# tuggerTrackerV1.net
KiCad netlist of a schematic drawn in EAGLE
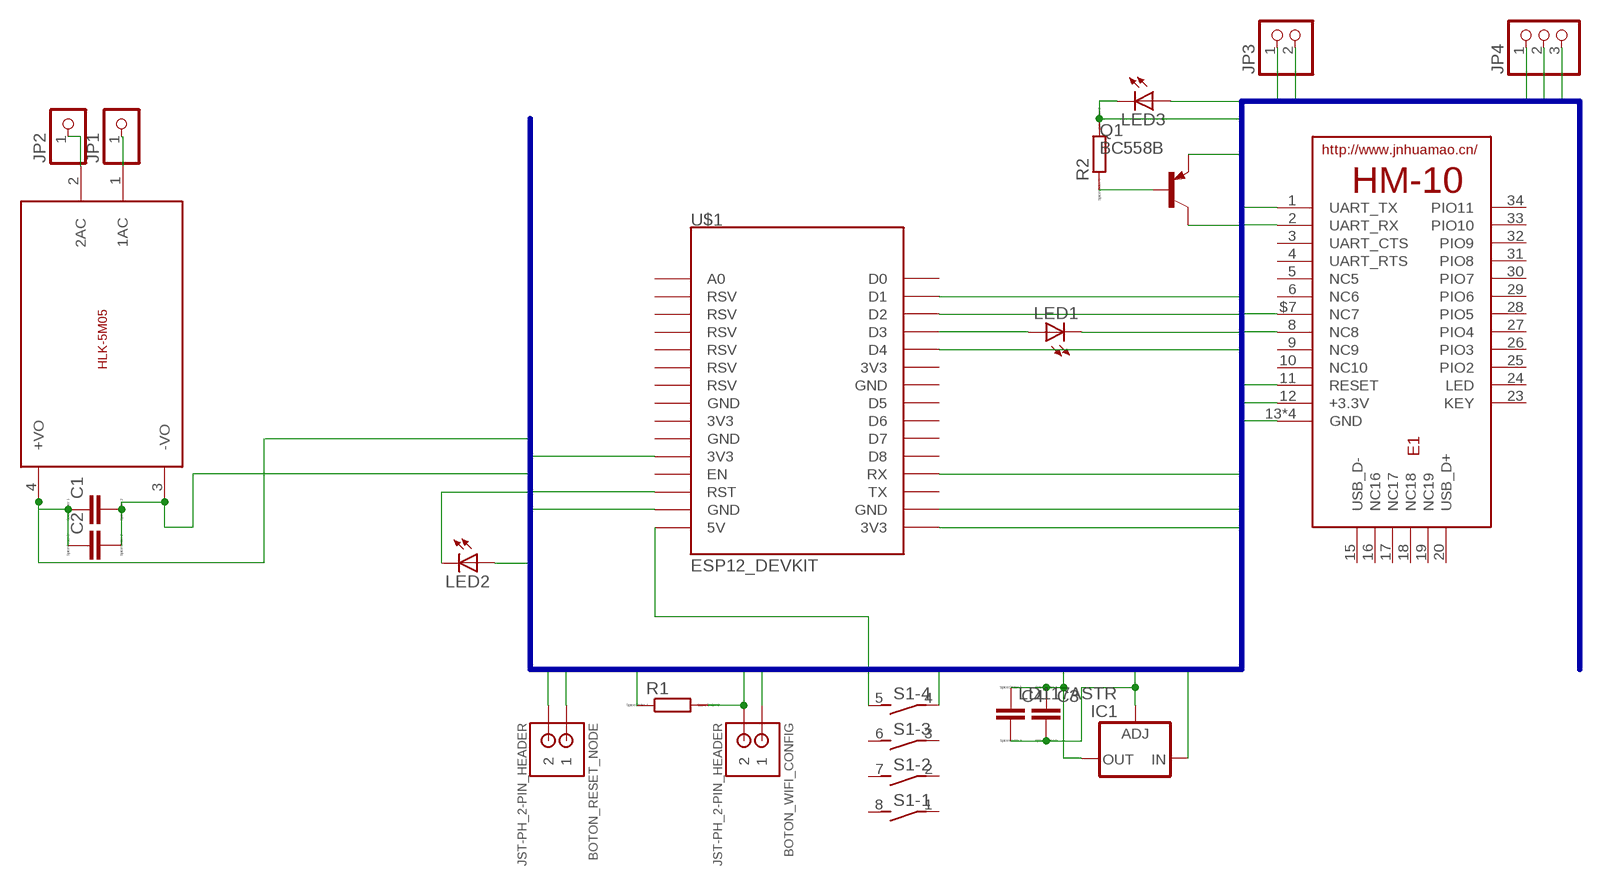
[diagram p0: schematic, sheet 1]

(export (version "E")
  (design (tool "Eeschema 10.0.6"))
  (components
    (comp (ref "BOTON_RESET_NODE")
      (value "JST-PH_2-PIN_HEADER")
      (footprint "eagle-import:JST_B2B-PH_HEADER")
      (libsource (lib "eagle-import") (part "JST-PH_2-PIN_HEADER"))
    )
    (comp (ref "BOTON_WIFI_CONFIG")
      (value "JST-PH_2-PIN_HEADER")
      (footprint "eagle-import:JST_B2B-PH_HEADER")
      (libsource (lib "eagle-import") (part "JST-PH_2-PIN_HEADER"))
    )
    (comp (ref "C1")
      (value "CC0603")
      (footprint "eagle-import:C0603")
      (libsource (lib "eagle-import") (part "CC0603"))
    )
    (comp (ref "C2")
      (value "CC0603")
      (footprint "eagle-import:C0603")
      (libsource (lib "eagle-import") (part "CC0603"))
    )
    (comp (ref "C3")
      (value "CC0603")
      (footprint "eagle-import:C0603")
      (libsource (lib "eagle-import") (part "CC0603"))
    )
    (comp (ref "C4")
      (value "CC0603")
      (footprint "eagle-import:C0603")
      (libsource (lib "eagle-import") (part "CC0603"))
    )
    (comp (ref "E1")
      (value "HM-10-BOARD")
      (footprint "eagle-import:26.9X13X2.2_BOARD")
      (libsource (lib "eagle-import") (part "HM-10-BOARD"))
    )
    (comp (ref "IC1")
      (value "LD117ASTR")
      (footprint "eagle-import:SOT223")
      (libsource (lib "eagle-import") (part "LD117A?STR"))
    )
    (comp (ref "JP1")
      (value "PINHD-1X1")
      (footprint "eagle-import:1X01")
      (libsource (lib "eagle-import") (part "PINHD-1X1"))
    )
    (comp (ref "JP2")
      (value "PINHD-1X1")
      (footprint "eagle-import:1X01")
      (libsource (lib "eagle-import") (part "PINHD-1X1"))
    )
    (comp (ref "JP3")
      (value "PINHD-1X2")
      (footprint "eagle-import:1X02")
      (libsource (lib "eagle-import") (part "PINHD-1X2"))
    )
    (comp (ref "JP4")
      (value "PINHD-1X3")
      (footprint "eagle-import:1X03")
      (libsource (lib "eagle-import") (part "PINHD-1X3"))
    )
    (comp (ref "LED1")
      (value "LEDCHIPLED_1206")
      (footprint "eagle-import:CHIPLED_1206")
      (libsource (lib "eagle-import") (part "LEDCHIPLED_1206"))
    )
    (comp (ref "LED2")
      (value "LEDCHIPLED_1206")
      (footprint "eagle-import:CHIPLED_1206")
      (libsource (lib "eagle-import") (part "LEDCHIPLED_1206"))
    )
    (comp (ref "LED3")
      (value "LEDCHIPLED_1206")
      (footprint "eagle-import:CHIPLED_1206")
      (libsource (lib "eagle-import") (part "LEDCHIPLED_1206"))
    )
    (comp (ref "Q1")
      (value "BC558B")
      (footprint "eagle-import:TO92-EBC")
      (libsource (lib "eagle-import") (part "BC558B"))
    )
    (comp (ref "R1")
      (value "R0207/10")
      (footprint "eagle-import:0207_10")
      (libsource (lib "eagle-import") (part "R0207/10"))
    )
    (comp (ref "R2")
      (value "R0207/10")
      (footprint "eagle-import:0207_10")
      (libsource (lib "eagle-import") (part "R0207/10"))
    )
    (comp (ref "S1")
      (value "DIP04S")
      (footprint "eagle-import:DIP04S")
      (libsource (lib "eagle-import") (part "DIP04S"))
    )
    (comp (ref "U$1")
      (value "ESP12_DEVKIT")
      (footprint "eagle-import:ESP12_DEVKIT")
      (libsource (lib "eagle-import") (part "ESP12_DEVKIT"))
    )
    (comp (ref "U$2")
      (value "5VDC/5W")
      (footprint "eagle-import:HLK-5M05")
      (libsource (lib "eagle-import") (part "HLK-5M05"))
    )
  )
  (nets
    (net (code "1") (name "/BTPG1") (class "Default")
      (node (ref "E1") (pin "$7") (pinfunction "NC7_$7") (pintype "bidirectional"))
      (node (ref "JP4") (pin "1") (pinfunction "1_1") (pintype "passive"))
    )
    (net (code "2") (name "/BTPG2") (class "Default")
      (node (ref "E1") (pin "8") (pinfunction "NC8_8") (pintype "bidirectional"))
      (node (ref "JP4") (pin "2") (pinfunction "2_2") (pintype "passive"))
    )
    (net (code "3") (name "/BTRST") (class "Default")
      (node (ref "E1") (pin "11") (pinfunction "RESET_11") (pintype "bidirectional"))
      (node (ref "JP4") (pin "3") (pinfunction "3_3") (pintype "passive"))
    )
    (net (code "4") (name "/BTVCC") (class "Default")
      (node (ref "E1") (pin "12") (pinfunction "+3.3V_12") (pintype "bidirectional"))
      (node (ref "Q1") (pin "C") (pinfunction "C_C") (pintype "passive"))
    )
    (net (code "5") (name "/D1") (class "Default")
      (node (ref "LED3") (pin "C") (pinfunction "C_C") (pintype "passive"))
      (node (ref "R2") (pin "2") (pinfunction "2_2") (pintype "passive"))
      (node (ref "U$1") (pin "D1") (pinfunction "D1_D1") (pintype "bidirectional"))
    )
    (net (code "6") (name "/D2") (class "Default")
      (node (ref "BOTON_WIFI_CONFIG") (pin "P2") (pinfunction "2_P2") (pintype "bidirectional"))
      (node (ref "R1") (pin "2") (pinfunction "2_2") (pintype "passive"))
      (node (ref "U$1") (pin "D2") (pinfunction "D2_D2") (pintype "bidirectional"))
    )
    (net (code "7") (name "/GND") (class "Default")
      (node (ref "BOTON_RESET_NODE") (pin "P2") (pinfunction "2_P2") (pintype "bidirectional"))
      (node (ref "C1") (pin "2") (pinfunction "2_2") (pintype "passive"))
      (node (ref "C2") (pin "2") (pinfunction "2_2") (pintype "passive"))
      (node (ref "C3") (pin "2") (pinfunction "2_2") (pintype "passive"))
      (node (ref "C4") (pin "2") (pinfunction "2_2") (pintype "passive"))
      (node (ref "E1") (pin "13") (pinfunction "GND_13") (pintype "bidirectional"))
      (node (ref "E1") (pin "14") (pinfunction "GND_14") (pintype "bidirectional"))
      (node (ref "E1") (pin "21") (pinfunction "GND_21") (pintype "bidirectional"))
      (node (ref "E1") (pin "22") (pinfunction "GND_22") (pintype "bidirectional"))
      (node (ref "IC1") (pin "1") (pinfunction "ADJ_1") (pintype "input"))
      (node (ref "JP3") (pin "1") (pinfunction "1_1") (pintype "passive"))
      (node (ref "LED1") (pin "C") (pinfunction "C_C") (pintype "passive"))
      (node (ref "LED2") (pin "C") (pinfunction "C_C") (pintype "passive"))
      (node (ref "R1") (pin "1") (pinfunction "1_1") (pintype "passive"))
      (node (ref "U$1") (pin "GND@1") (pinfunction "GND_GND@1") (pintype "bidirectional"))
      (node (ref "U$1") (pin "GND@3") (pinfunction "GND_GND@3") (pintype "bidirectional"))
      (node (ref "U$2") (pin "3") (pinfunction "-VO_3") (pintype "bidirectional"))
    )
    (net (code "8") (name "/NODRST") (class "Default")
      (node (ref "BOTON_RESET_NODE") (pin "P1") (pinfunction "1_P1") (pintype "bidirectional"))
      (node (ref "U$1") (pin "RST") (pinfunction "RST_RST") (pintype "bidirectional"))
    )
    (net (code "9") (name "/NRXBTX") (class "Default")
      (node (ref "E1") (pin "1") (pinfunction "UART_TX_1") (pintype "bidirectional"))
      (node (ref "U$1") (pin "RX") (pinfunction "RX_RX") (pintype "bidirectional"))
    )
    (net (code "10") (name "/NTXBRX") (class "Default")
      (node (ref "E1") (pin "2") (pinfunction "UART_RX_2") (pintype "bidirectional"))
      (node (ref "U$1") (pin "D4") (pinfunction "D4_D4") (pintype "bidirectional"))
    )
    (net (code "11") (name "/V3NODE") (class "Default")
      (node (ref "BOTON_WIFI_CONFIG") (pin "P1") (pinfunction "1_P1") (pintype "bidirectional"))
      (node (ref "LED2") (pin "A") (pinfunction "A_A") (pintype "passive"))
      (node (ref "LED3") (pin "A") (pinfunction "A_A") (pintype "passive"))
      (node (ref "U$1") (pin "3V3@0") (pinfunction "3V3_3V3@0") (pintype "bidirectional"))
      (node (ref "U$1") (pin "3V3@2") (pinfunction "3V3_3V3@2") (pintype "bidirectional"))
    )
    (net (code "12") (name "/V3REG") (class "Default")
      (node (ref "C3") (pin "1") (pinfunction "1_1") (pintype "passive"))
      (node (ref "C4") (pin "1") (pinfunction "1_1") (pintype "passive"))
      (node (ref "IC1") (pin "4") (pinfunction "OUT_4") (pintype "passive"))
      (node (ref "Q1") (pin "E") (pinfunction "E_E") (pintype "passive"))
    )
    (net (code "13") (name "/VIN") (class "Default")
      (node (ref "C1") (pin "1") (pinfunction "1_1") (pintype "passive"))
      (node (ref "C2") (pin "1") (pinfunction "1_1") (pintype "passive"))
      (node (ref "IC1") (pin "3") (pinfunction "IN_3") (pintype "input"))
      (node (ref "JP3") (pin "2") (pinfunction "2_2") (pintype "passive"))
      (node (ref "S1") (pin "4") (pinfunction "1_4") (pintype "passive"))
      (node (ref "U$2") (pin "4") (pinfunction "+VO_4") (pintype "bidirectional"))
    )
    (net (code "14") (name "Net-(LED1-PadA)") (class "Default")
      (node (ref "LED1") (pin "A") (pinfunction "A_A") (pintype "passive"))
      (node (ref "U$1") (pin "D3") (pinfunction "D3_D3") (pintype "bidirectional"))
    )
    (net (code "15") (name "Net-(Q1-PadB)") (class "Default")
      (node (ref "Q1") (pin "B") (pinfunction "B_B") (pintype "passive"))
      (node (ref "R2") (pin "1") (pinfunction "1_1") (pintype "passive"))
    )
    (net (code "16") (name "Net-(S1D-2)") (class "Default")
      (node (ref "S1") (pin "5") (pinfunction "2_5") (pintype "passive"))
      (node (ref "U$1") (pin "5V") (pinfunction "5V_5V") (pintype "bidirectional"))
    )
    (net (code "17") (name "Net-(U$2-1AC)") (class "Default")
      (node (ref "JP1") (pin "1") (pinfunction "1_1") (pintype "passive"))
      (node (ref "U$2") (pin "1") (pinfunction "1AC_1") (pintype "bidirectional"))
    )
    (net (code "18") (name "Net-(U$2-2AC)") (class "Default")
      (node (ref "JP2") (pin "1") (pinfunction "1_1") (pintype "passive"))
      (node (ref "U$2") (pin "2") (pinfunction "2AC_2") (pintype "bidirectional"))
    )
    (net (code "19") (name "unconnected-(E1-KEY-Pad23)") (class "Default")
      (node (ref "E1") (pin "23") (pinfunction "KEY_23") (pintype "bidirectional"))
    )
    (net (code "20") (name "unconnected-(E1-LED-Pad24)") (class "Default")
      (node (ref "E1") (pin "24") (pinfunction "LED_24") (pintype "bidirectional"))
    )
    (net (code "21") (name "unconnected-(E1-NC5-Pad5)") (class "Default")
      (node (ref "E1") (pin "5") (pinfunction "NC5_5") (pintype "bidirectional"))
    )
    (net (code "22") (name "unconnected-(E1-NC6-Pad6)") (class "Default")
      (node (ref "E1") (pin "6") (pinfunction "NC6_6") (pintype "bidirectional"))
    )
    (net (code "23") (name "unconnected-(E1-NC9-Pad9)") (class "Default")
      (node (ref "E1") (pin "9") (pinfunction "NC9_9") (pintype "bidirectional"))
    )
    (net (code "24") (name "unconnected-(E1-NC10-Pad10)") (class "Default")
      (node (ref "E1") (pin "10") (pinfunction "NC10_10") (pintype "bidirectional"))
    )
    (net (code "25") (name "unconnected-(E1-NC16-Pad16)") (class "Default")
      (node (ref "E1") (pin "16") (pinfunction "NC16_16") (pintype "bidirectional"))
    )
    (net (code "26") (name "unconnected-(E1-NC17-Pad17)") (class "Default")
      (node (ref "E1") (pin "17") (pinfunction "NC17_17") (pintype "bidirectional"))
    )
    (net (code "27") (name "unconnected-(E1-NC18-Pad18)") (class "Default")
      (node (ref "E1") (pin "18") (pinfunction "NC18_18") (pintype "bidirectional"))
    )
    (net (code "28") (name "unconnected-(E1-NC19-Pad19)") (class "Default")
      (node (ref "E1") (pin "19") (pinfunction "NC19_19") (pintype "bidirectional"))
    )
    (net (code "29") (name "unconnected-(E1-PIO2-Pad25)") (class "Default")
      (node (ref "E1") (pin "25") (pinfunction "PIO2_25") (pintype "bidirectional"))
    )
    (net (code "30") (name "unconnected-(E1-PIO3-Pad26)") (class "Default")
      (node (ref "E1") (pin "26") (pinfunction "PIO3_26") (pintype "bidirectional"))
    )
    (net (code "31") (name "unconnected-(E1-PIO4-Pad27)") (class "Default")
      (node (ref "E1") (pin "27") (pinfunction "PIO4_27") (pintype "bidirectional"))
    )
    (net (code "32") (name "unconnected-(E1-PIO5-Pad28)") (class "Default")
      (node (ref "E1") (pin "28") (pinfunction "PIO5_28") (pintype "bidirectional"))
    )
    (net (code "33") (name "unconnected-(E1-PIO6-Pad29)") (class "Default")
      (node (ref "E1") (pin "29") (pinfunction "PIO6_29") (pintype "bidirectional"))
    )
    (net (code "34") (name "unconnected-(E1-PIO7-Pad30)") (class "Default")
      (node (ref "E1") (pin "30") (pinfunction "PIO7_30") (pintype "bidirectional"))
    )
    (net (code "35") (name "unconnected-(E1-PIO8-Pad31)") (class "Default")
      (node (ref "E1") (pin "31") (pinfunction "PIO8_31") (pintype "bidirectional"))
    )
    (net (code "36") (name "unconnected-(E1-PIO9-Pad32)") (class "Default")
      (node (ref "E1") (pin "32") (pinfunction "PIO9_32") (pintype "bidirectional"))
    )
    (net (code "37") (name "unconnected-(E1-PIO10-Pad33)") (class "Default")
      (node (ref "E1") (pin "33") (pinfunction "PIO10_33") (pintype "bidirectional"))
    )
    (net (code "38") (name "unconnected-(E1-PIO11-Pad34)") (class "Default")
      (node (ref "E1") (pin "34") (pinfunction "PIO11_34") (pintype "bidirectional"))
    )
    (net (code "39") (name "unconnected-(E1-UART_CTS-Pad3)") (class "Default")
      (node (ref "E1") (pin "3") (pinfunction "UART_CTS_3") (pintype "bidirectional"))
    )
    (net (code "40") (name "unconnected-(E1-UART_RTS-Pad4)") (class "Default")
      (node (ref "E1") (pin "4") (pinfunction "UART_RTS_4") (pintype "bidirectional"))
    )
    (net (code "41") (name "unconnected-(E1-USB_D+-Pad20)") (class "Default")
      (node (ref "E1") (pin "20") (pinfunction "USB_D+_20") (pintype "bidirectional"))
    )
    (net (code "42") (name "unconnected-(E1-USB_D--Pad15)") (class "Default")
      (node (ref "E1") (pin "15") (pinfunction "USB_D-_15") (pintype "bidirectional"))
    )
    (net (code "43") (name "unconnected-(S1-Pad1)") (class "Default")
      (node (ref "S1") (pin "1") (pinfunction "1_1") (pintype "passive"))
    )
    (net (code "44") (name "unconnected-(S1A-2-Pad8)") (class "Default")
      (node (ref "S1") (pin "8") (pinfunction "2_8") (pintype "passive"))
    )
    (net (code "45") (name "unconnected-(S1B-1-Pad2)") (class "Default")
      (node (ref "S1") (pin "2") (pinfunction "1_2") (pintype "passive"))
    )
    (net (code "46") (name "unconnected-(S1B-2-Pad7)") (class "Default")
      (node (ref "S1") (pin "7") (pinfunction "2_7") (pintype "passive"))
    )
    (net (code "47") (name "unconnected-(S1C-1-Pad3)") (class "Default")
      (node (ref "S1") (pin "3") (pinfunction "1_3") (pintype "passive"))
    )
    (net (code "48") (name "unconnected-(S1C-2-Pad6)") (class "Default")
      (node (ref "S1") (pin "6") (pinfunction "2_6") (pintype "passive"))
    )
    (net (code "49") (name "unconnected-(U$1-3V3-Pad3V3@1)") (class "Default")
      (node (ref "U$1") (pin "3V3@1") (pinfunction "3V3_3V3@1") (pintype "bidirectional"))
    )
    (net (code "50") (name "unconnected-(U$1-3V3-Pad3V3@3)") (class "Default")
      (node (ref "U$1") (pin "3V3@3") (pinfunction "3V3_3V3@3") (pintype "bidirectional"))
    )
    (net (code "51") (name "unconnected-(U$1-GND-PadGND@0)") (class "Default")
      (node (ref "U$1") (pin "GND@0") (pinfunction "GND_GND@0") (pintype "bidirectional"))
    )
    (net (code "52") (name "unconnected-(U$1-GND-PadGND@2)") (class "Default")
      (node (ref "U$1") (pin "GND@2") (pinfunction "GND_GND@2") (pintype "bidirectional"))
    )
    (net (code "53") (name "unconnected-(U$1-GND-PadGND@4)") (class "Default")
      (node (ref "U$1") (pin "GND@4") (pinfunction "GND_GND@4") (pintype "bidirectional"))
    )
    (net (code "54") (name "unconnected-(U$1-PadA0)") (class "Default")
      (node (ref "U$1") (pin "A0") (pinfunction "A0_A0") (pintype "bidirectional"))
    )
    (net (code "55") (name "unconnected-(U$1-PadD0)") (class "Default")
      (node (ref "U$1") (pin "D0") (pinfunction "D0_D0") (pintype "bidirectional"))
    )
    (net (code "56") (name "unconnected-(U$1-PadD5)") (class "Default")
      (node (ref "U$1") (pin "D5") (pinfunction "D5_D5") (pintype "bidirectional"))
    )
    (net (code "57") (name "unconnected-(U$1-PadD6)") (class "Default")
      (node (ref "U$1") (pin "D6") (pinfunction "D6_D6") (pintype "bidirectional"))
    )
    (net (code "58") (name "unconnected-(U$1-PadD7)") (class "Default")
      (node (ref "U$1") (pin "D7") (pinfunction "D7_D7") (pintype "bidirectional"))
    )
    (net (code "59") (name "unconnected-(U$1-PadD8)") (class "Default")
      (node (ref "U$1") (pin "D8") (pinfunction "D8_D8") (pintype "bidirectional"))
    )
    (net (code "60") (name "unconnected-(U$1-PadEN)") (class "Default")
      (node (ref "U$1") (pin "EN") (pinfunction "EN_EN") (pintype "bidirectional"))
    )
    (net (code "61") (name "unconnected-(U$1-PadTX)") (class "Default")
      (node (ref "U$1") (pin "TX") (pinfunction "TX_TX") (pintype "bidirectional"))
    )
    (net (code "62") (name "unconnected-(U$1-RSV-PadRSV@0)") (class "Default")
      (node (ref "U$1") (pin "RSV@0") (pinfunction "RSV_RSV@0") (pintype "bidirectional"))
    )
    (net (code "63") (name "unconnected-(U$1-RSV-PadRSV@1)") (class "Default")
      (node (ref "U$1") (pin "RSV@1") (pinfunction "RSV_RSV@1") (pintype "bidirectional"))
    )
    (net (code "64") (name "unconnected-(U$1-RSV-PadRSV@2)") (class "Default")
      (node (ref "U$1") (pin "RSV@2") (pinfunction "RSV_RSV@2") (pintype "bidirectional"))
    )
    (net (code "65") (name "unconnected-(U$1-RSV-PadRSV@3)") (class "Default")
      (node (ref "U$1") (pin "RSV@3") (pinfunction "RSV_RSV@3") (pintype "bidirectional"))
    )
    (net (code "66") (name "unconnected-(U$1-RSV-PadRSV@4)") (class "Default")
      (node (ref "U$1") (pin "RSV@4") (pinfunction "RSV_RSV@4") (pintype "bidirectional"))
    )
    (net (code "67") (name "unconnected-(U$1-RSV-PadRSV@5)") (class "Default")
      (node (ref "U$1") (pin "RSV@5") (pinfunction "RSV_RSV@5") (pintype "bidirectional"))
    )
  )
)
